# SCH1.net
KiCad netlist of a schematic drawn in EAGLE
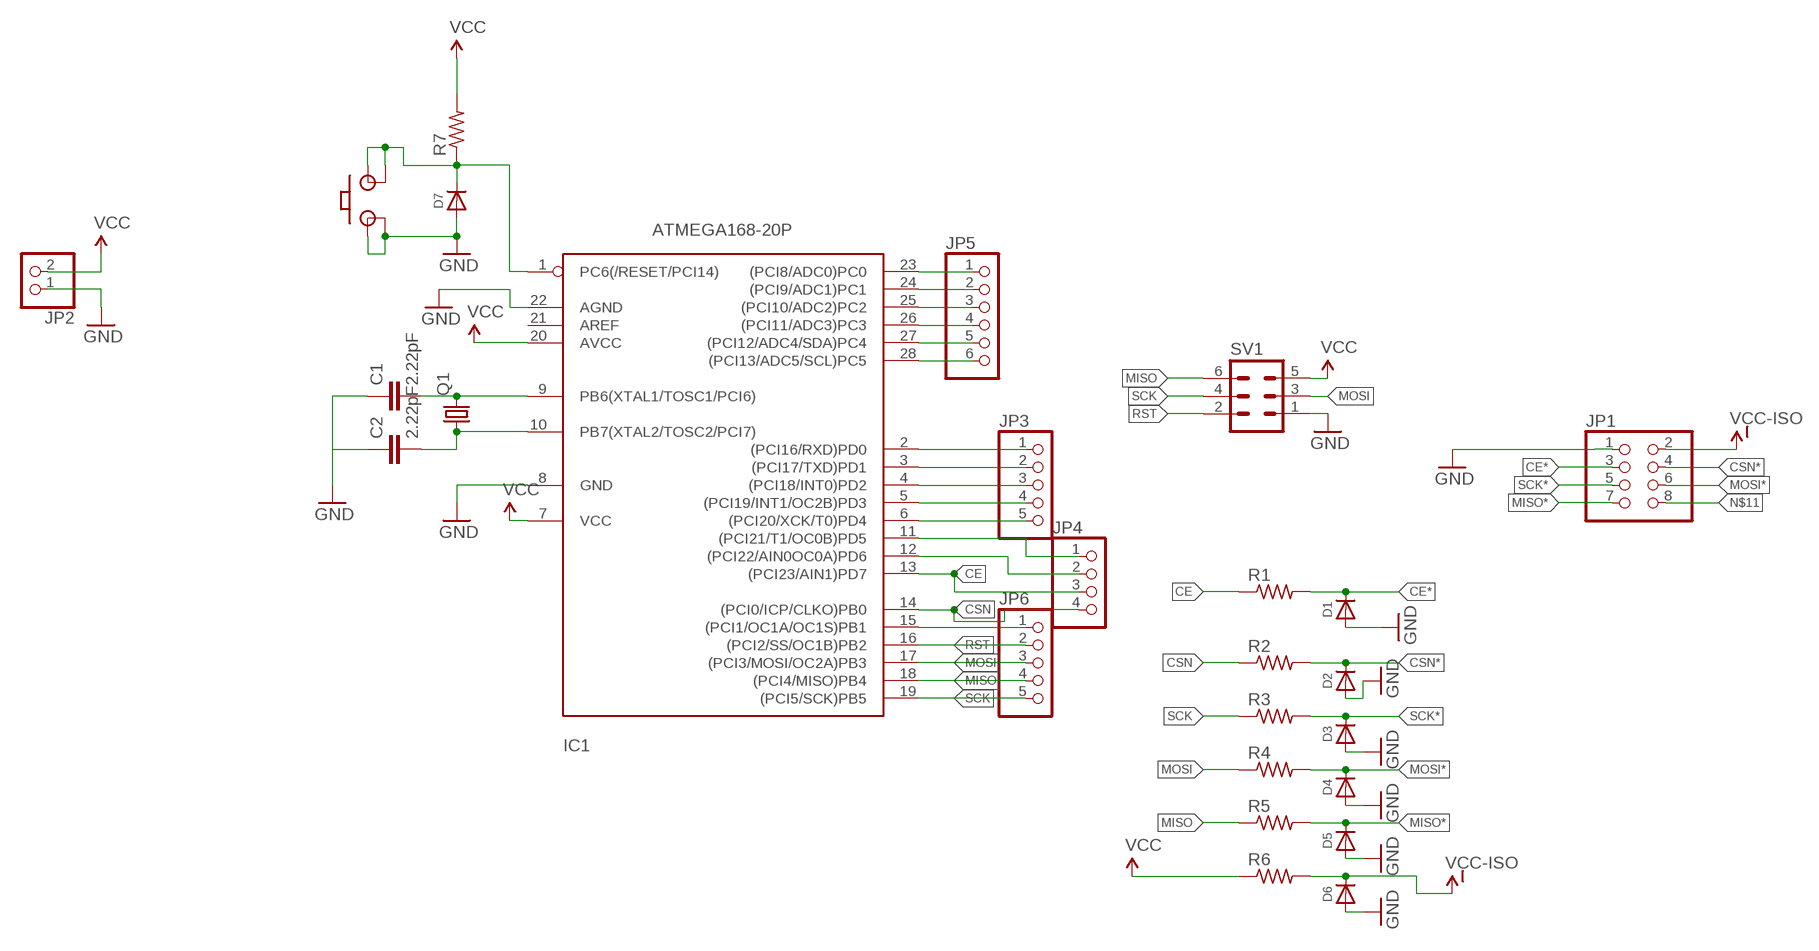
[diagram p0: schematic, sheet 1]

(export (version "E")
  (design (tool "Eeschema 10.0.6"))
  (components
    (comp (ref "C1")
      (value "2.22pF")
      (footprint "eagle-import:C025-024X044")
      (libsource (lib "eagle-import") (part "C-EU025-024X044"))
    )
    (comp (ref "C2")
      (value "2.22pF")
      (footprint "eagle-import:C025-024X044")
      (libsource (lib "eagle-import") (part "C-EU025-024X044"))
    )
    (comp (ref "D1")
      (value "DIODEDO-1N4148")
      (footprint "eagle-import:DO-1N4148")
      (libsource (lib "eagle-import") (part "DIODEDO-1N4148"))
    )
    (comp (ref "D2")
      (value "DIODEDO-1N4148")
      (footprint "eagle-import:DO-1N4148")
      (libsource (lib "eagle-import") (part "DIODEDO-1N4148"))
    )
    (comp (ref "D3")
      (value "DIODEDO-1N4148")
      (footprint "eagle-import:DO-1N4148")
      (libsource (lib "eagle-import") (part "DIODEDO-1N4148"))
    )
    (comp (ref "D4")
      (value "DIODEDO-1N4148")
      (footprint "eagle-import:DO-1N4148")
      (libsource (lib "eagle-import") (part "DIODEDO-1N4148"))
    )
    (comp (ref "D5")
      (value "DIODEDO-1N4148")
      (footprint "eagle-import:DO-1N4148")
      (libsource (lib "eagle-import") (part "DIODEDO-1N4148"))
    )
    (comp (ref "D6")
      (value "DIODEDO-1N4148")
      (footprint "eagle-import:DO-1N4148")
      (libsource (lib "eagle-import") (part "DIODEDO-1N4148"))
    )
    (comp (ref "D7")
      (value "DIODEDO-1N4148")
      (footprint "eagle-import:DO-1N4148")
      (libsource (lib "eagle-import") (part "DIODEDO-1N4148"))
    )
    (comp (ref "IC1")
      (value "ATMEGA168-20P")
      (footprint "eagle-import:DIL28-3")
      (libsource (lib "eagle-import") (part "ATMEGA168P-20"))
    )
    (comp (ref "JP1")
      (value "PINHD-2X4")
      (footprint "eagle-import:2X04")
      (libsource (lib "eagle-import") (part "PINHD-2X4"))
    )
    (comp (ref "JP2")
      (value "PINHD-1X2")
      (footprint "eagle-import:1X02")
      (libsource (lib "eagle-import") (part "PINHD-1X2"))
    )
    (comp (ref "JP3")
      (value "PINHD-1X5")
      (footprint "eagle-import:1X05")
      (libsource (lib "eagle-import") (part "PINHD-1X5"))
    )
    (comp (ref "JP4")
      (value "PINHD-1X4")
      (footprint "eagle-import:1X04")
      (libsource (lib "eagle-import") (part "PINHD-1X4"))
    )
    (comp (ref "JP5")
      (value "PINHD-1X6")
      (footprint "eagle-import:1X06")
      (libsource (lib "eagle-import") (part "PINHD-1X6"))
    )
    (comp (ref "JP6")
      (value "PINHD-1X5")
      (footprint "eagle-import:1X05")
      (libsource (lib "eagle-import") (part "PINHD-1X5"))
    )
    (comp (ref "PB1")
      (value "TACTSW")
      (footprint "eagle-import:TACTSW")
      (libsource (lib "eagle-import") (part "TACTSW"))
    )
    (comp (ref "Q1")
      (value "CRYSTALHC49U-V")
      (footprint "eagle-import:HC49U-V")
      (libsource (lib "eagle-import") (part "CRYSTALHC49U-V"))
    )
    (comp (ref "R1")
      (value "R-US_0207/7")
      (footprint "eagle-import:0207_7")
      (libsource (lib "eagle-import") (part "R-US_0207/7"))
    )
    (comp (ref "R2")
      (value "R-US_0207/7")
      (footprint "eagle-import:0207_7")
      (libsource (lib "eagle-import") (part "R-US_0207/7"))
    )
    (comp (ref "R3")
      (value "R-US_0207/7")
      (footprint "eagle-import:0207_7")
      (libsource (lib "eagle-import") (part "R-US_0207/7"))
    )
    (comp (ref "R4")
      (value "R-US_0207/7")
      (footprint "eagle-import:0207_7")
      (libsource (lib "eagle-import") (part "R-US_0207/7"))
    )
    (comp (ref "R5")
      (value "R-US_0207/7")
      (footprint "eagle-import:0207_7")
      (libsource (lib "eagle-import") (part "R-US_0207/7"))
    )
    (comp (ref "R6")
      (value "R-US_0207/7")
      (footprint "eagle-import:0207_7")
      (libsource (lib "eagle-import") (part "R-US_0207/7"))
    )
    (comp (ref "R7")
      (value "R-US_0207/7")
      (footprint "eagle-import:0207_7")
      (libsource (lib "eagle-import") (part "R-US_0207/7"))
    )
    (comp (ref "SV1")
      (value "MA03-2")
      (footprint "eagle-import:MA03-2")
      (libsource (lib "eagle-import") (part "MA03-2"))
    )
  )
  (nets
    (net (code "1") (name "CE") (class "Default")
      (node (ref "IC1") (pin "13") (pinfunction "(PCI23/AIN1)PD7_13") (pintype "bidirectional"))
      (node (ref "JP4") (pin "3") (pinfunction "3_3") (pintype "passive"))
      (node (ref "R1") (pin "1") (pinfunction "1_1") (pintype "passive"))
    )
    (net (code "2") (name "CE*") (class "Default")
      (node (ref "D1") (pin "C") (pinfunction "C_C") (pintype "passive"))
      (node (ref "JP1") (pin "3") (pinfunction "3_3") (pintype "passive"))
      (node (ref "R1") (pin "2") (pinfunction "2_2") (pintype "passive"))
    )
    (net (code "3") (name "CSN") (class "Default")
      (node (ref "IC1") (pin "14") (pinfunction "(PCI0/ICP/CLKO)PB0_14") (pintype "bidirectional"))
      (node (ref "JP4") (pin "4") (pinfunction "4_4") (pintype "passive"))
      (node (ref "R2") (pin "1") (pinfunction "1_1") (pintype "passive"))
    )
    (net (code "4") (name "CSN*") (class "Default")
      (node (ref "D2") (pin "C") (pinfunction "C_C") (pintype "passive"))
      (node (ref "JP1") (pin "4") (pinfunction "4_4") (pintype "passive"))
      (node (ref "R2") (pin "2") (pinfunction "2_2") (pintype "passive"))
    )
    (net (code "5") (name "GND") (class "Default")
      (node (ref "C1") (pin "1") (pinfunction "1_1") (pintype "passive"))
      (node (ref "C2") (pin "1") (pinfunction "1_1") (pintype "passive"))
      (node (ref "D1") (pin "A") (pinfunction "A_A") (pintype "passive"))
      (node (ref "D2") (pin "A") (pinfunction "A_A") (pintype "passive"))
      (node (ref "D3") (pin "A") (pinfunction "A_A") (pintype "passive"))
      (node (ref "D4") (pin "A") (pinfunction "A_A") (pintype "passive"))
      (node (ref "D5") (pin "A") (pinfunction "A_A") (pintype "passive"))
      (node (ref "D6") (pin "A") (pinfunction "A_A") (pintype "passive"))
      (node (ref "D7") (pin "A") (pinfunction "A_A") (pintype "passive"))
      (node (ref "IC1") (pin "22") (pinfunction "AGND_22") (pintype "bidirectional"))
      (node (ref "IC1") (pin "8") (pinfunction "GND_8") (pintype "bidirectional"))
      (node (ref "JP1") (pin "1") (pinfunction "1_1") (pintype "passive"))
      (node (ref "JP2") (pin "1") (pinfunction "1_1") (pintype "passive"))
      (node (ref "PB1") (pin "P$1") (pinfunction "P$1_P$1") (pintype "passive"))
      (node (ref "PB1") (pin "P$2") (pinfunction "P$3_P$2") (pintype "passive"))
      (node (ref "SV1") (pin "1") (pinfunction "1_1") (pintype "passive"))
    )
    (net (code "6") (name "MISO") (class "Default")
      (node (ref "IC1") (pin "18") (pinfunction "(PCI4/MISO)PB4_18") (pintype "bidirectional"))
      (node (ref "JP6") (pin "4") (pinfunction "4_4") (pintype "passive"))
      (node (ref "R5") (pin "1") (pinfunction "1_1") (pintype "passive"))
      (node (ref "SV1") (pin "6") (pinfunction "6_6") (pintype "passive"))
    )
    (net (code "7") (name "MISO*") (class "Default")
      (node (ref "D5") (pin "C") (pinfunction "C_C") (pintype "passive"))
      (node (ref "JP1") (pin "7") (pinfunction "7_7") (pintype "passive"))
      (node (ref "R5") (pin "2") (pinfunction "2_2") (pintype "passive"))
    )
    (net (code "8") (name "MOSI") (class "Default")
      (node (ref "IC1") (pin "17") (pinfunction "(PCI3/MOSI/OC2A)PB3_17") (pintype "bidirectional"))
      (node (ref "JP6") (pin "3") (pinfunction "3_3") (pintype "passive"))
      (node (ref "R4") (pin "1") (pinfunction "1_1") (pintype "passive"))
      (node (ref "SV1") (pin "3") (pinfunction "3_3") (pintype "passive"))
    )
    (net (code "9") (name "MOSI*") (class "Default")
      (node (ref "D4") (pin "C") (pinfunction "C_C") (pintype "passive"))
      (node (ref "JP1") (pin "6") (pinfunction "6_6") (pintype "passive"))
      (node (ref "R4") (pin "2") (pinfunction "2_2") (pintype "passive"))
    )
    (net (code "10") (name "N$11") (class "Default")
      (node (ref "JP1") (pin "8") (pinfunction "8_8") (pintype "passive"))
    )
    (net (code "11") (name "Net-(IC1-(PCI1{slash}OC1A{slash}OC1S)PB1)") (class "Default")
      (node (ref "IC1") (pin "15") (pinfunction "(PCI1/OC1A/OC1S)PB1_15") (pintype "bidirectional"))
      (node (ref "JP6") (pin "1") (pinfunction "1_1") (pintype "passive"))
    )
    (net (code "12") (name "Net-(IC1-(PCI8{slash}ADC0)PC0)") (class "Default")
      (node (ref "IC1") (pin "23") (pinfunction "(PCI8/ADC0)PC0_23") (pintype "bidirectional"))
      (node (ref "JP5") (pin "1") (pinfunction "1_1") (pintype "passive"))
    )
    (net (code "13") (name "Net-(IC1-(PCI9{slash}ADC1)PC1)") (class "Default")
      (node (ref "IC1") (pin "24") (pinfunction "(PCI9/ADC1)PC1_24") (pintype "bidirectional"))
      (node (ref "JP5") (pin "2") (pinfunction "2_2") (pintype "passive"))
    )
    (net (code "14") (name "Net-(IC1-(PCI10{slash}ADC2)PC2)") (class "Default")
      (node (ref "IC1") (pin "25") (pinfunction "(PCI10/ADC2)PC2_25") (pintype "bidirectional"))
      (node (ref "JP5") (pin "3") (pinfunction "3_3") (pintype "passive"))
    )
    (net (code "15") (name "Net-(IC1-(PCI11{slash}ADC3)PC3)") (class "Default")
      (node (ref "IC1") (pin "26") (pinfunction "(PCI11/ADC3)PC3_26") (pintype "bidirectional"))
      (node (ref "JP5") (pin "4") (pinfunction "4_4") (pintype "passive"))
    )
    (net (code "16") (name "Net-(IC1-(PCI12{slash}ADC4{slash}SDA)PC4)") (class "Default")
      (node (ref "IC1") (pin "27") (pinfunction "(PCI12/ADC4/SDA)PC4_27") (pintype "bidirectional"))
      (node (ref "JP5") (pin "5") (pinfunction "5_5") (pintype "passive"))
    )
    (net (code "17") (name "Net-(IC1-(PCI13{slash}ADC5{slash}SCL)PC5)") (class "Default")
      (node (ref "IC1") (pin "28") (pinfunction "(PCI13/ADC5/SCL)PC5_28") (pintype "bidirectional"))
      (node (ref "JP5") (pin "6") (pinfunction "6_6") (pintype "passive"))
    )
    (net (code "18") (name "Net-(IC1-(PCI16{slash}RXD)PD0)") (class "Default")
      (node (ref "IC1") (pin "2") (pinfunction "(PCI16/RXD)PD0_2") (pintype "bidirectional"))
      (node (ref "JP3") (pin "1") (pinfunction "1_1") (pintype "passive"))
    )
    (net (code "19") (name "Net-(IC1-(PCI17{slash}TXD)PD1)") (class "Default")
      (node (ref "IC1") (pin "3") (pinfunction "(PCI17/TXD)PD1_3") (pintype "bidirectional"))
      (node (ref "JP3") (pin "2") (pinfunction "2_2") (pintype "passive"))
    )
    (net (code "20") (name "Net-(IC1-(PCI18{slash}INT0)PD2)") (class "Default")
      (node (ref "IC1") (pin "4") (pinfunction "(PCI18/INT0)PD2_4") (pintype "bidirectional"))
      (node (ref "JP3") (pin "3") (pinfunction "3_3") (pintype "passive"))
    )
    (net (code "21") (name "Net-(IC1-(PCI19{slash}INT1{slash}OC2B)PD3)") (class "Default")
      (node (ref "IC1") (pin "5") (pinfunction "(PCI19/INT1/OC2B)PD3_5") (pintype "bidirectional"))
      (node (ref "JP3") (pin "4") (pinfunction "4_4") (pintype "passive"))
    )
    (net (code "22") (name "Net-(IC1-(PCI20{slash}XCK{slash}T0)PD4)") (class "Default")
      (node (ref "IC1") (pin "6") (pinfunction "(PCI20/XCK/T0)PD4_6") (pintype "bidirectional"))
      (node (ref "JP3") (pin "5") (pinfunction "5_5") (pintype "passive"))
    )
    (net (code "23") (name "Net-(IC1-(PCI21{slash}T1{slash}OC0B)PD5)") (class "Default")
      (node (ref "IC1") (pin "11") (pinfunction "(PCI21/T1/OC0B)PD5_11") (pintype "bidirectional"))
      (node (ref "JP4") (pin "1") (pinfunction "1_1") (pintype "passive"))
    )
    (net (code "24") (name "Net-(IC1-(PCI22{slash}AIN0OC0A)PD6)") (class "Default")
      (node (ref "IC1") (pin "12") (pinfunction "(PCI22/AIN0OC0A)PD6_12") (pintype "bidirectional"))
      (node (ref "JP4") (pin "2") (pinfunction "2_2") (pintype "passive"))
    )
    (net (code "25") (name "Net-(IC1-PB6(XTAL1{slash}TOSC1{slash}PCI6))") (class "Default")
      (node (ref "C1") (pin "2") (pinfunction "2_2") (pintype "passive"))
      (node (ref "IC1") (pin "9") (pinfunction "PB6(XTAL1/TOSC1/PCI6)_9") (pintype "bidirectional"))
      (node (ref "Q1") (pin "2") (pinfunction "2_2") (pintype "passive"))
    )
    (net (code "26") (name "Net-(IC1-PB7(XTAL2{slash}TOSC2{slash}PCI7))") (class "Default")
      (node (ref "C2") (pin "2") (pinfunction "2_2") (pintype "passive"))
      (node (ref "IC1") (pin "10") (pinfunction "PB7(XTAL2/TOSC2/PCI7)_10") (pintype "bidirectional"))
      (node (ref "Q1") (pin "1") (pinfunction "1_1") (pintype "passive"))
    )
    (net (code "27") (name "Net-(IC1-PC6({slash}RESET{slash}PCI14))") (class "Default")
      (node (ref "D7") (pin "C") (pinfunction "C_C") (pintype "passive"))
      (node (ref "IC1") (pin "1") (pinfunction "PC6(/RESET/PCI14)_1") (pintype "bidirectional"))
      (node (ref "PB1") (pin "P$3") (pinfunction "P$2_P$3") (pintype "passive"))
      (node (ref "PB1") (pin "P$4") (pinfunction "P$4_P$4") (pintype "passive"))
      (node (ref "R7") (pin "1") (pinfunction "1_1") (pintype "passive"))
    )
    (net (code "28") (name "RST") (class "Default")
      (node (ref "IC1") (pin "16") (pinfunction "(PCI2/SS/OC1B)PB2_16") (pintype "bidirectional"))
      (node (ref "JP6") (pin "2") (pinfunction "2_2") (pintype "passive"))
      (node (ref "SV1") (pin "2") (pinfunction "2_2") (pintype "passive"))
    )
    (net (code "29") (name "SCK") (class "Default")
      (node (ref "IC1") (pin "19") (pinfunction "(PCI5/SCK)PB5_19") (pintype "bidirectional"))
      (node (ref "JP6") (pin "5") (pinfunction "5_5") (pintype "passive"))
      (node (ref "R3") (pin "1") (pinfunction "1_1") (pintype "passive"))
      (node (ref "SV1") (pin "4") (pinfunction "4_4") (pintype "passive"))
    )
    (net (code "30") (name "SCK*") (class "Default")
      (node (ref "D3") (pin "C") (pinfunction "C_C") (pintype "passive"))
      (node (ref "JP1") (pin "5") (pinfunction "5_5") (pintype "passive"))
      (node (ref "R3") (pin "2") (pinfunction "2_2") (pintype "passive"))
    )
    (net (code "31") (name "VCC") (class "Default")
      (node (ref "IC1") (pin "20") (pinfunction "AVCC_20") (pintype "bidirectional"))
      (node (ref "IC1") (pin "7") (pinfunction "VCC_7") (pintype "bidirectional"))
      (node (ref "JP2") (pin "2") (pinfunction "2_2") (pintype "passive"))
      (node (ref "R6") (pin "1") (pinfunction "1_1") (pintype "passive"))
      (node (ref "R7") (pin "2") (pinfunction "2_2") (pintype "passive"))
      (node (ref "SV1") (pin "5") (pinfunction "5_5") (pintype "passive"))
    )
    (net (code "32") (name "VCC-ISO") (class "Default")
      (node (ref "D6") (pin "C") (pinfunction "C_C") (pintype "passive"))
      (node (ref "JP1") (pin "2") (pinfunction "2_2") (pintype "passive"))
      (node (ref "R6") (pin "2") (pinfunction "2_2") (pintype "passive"))
    )
    (net (code "33") (name "unconnected-(IC1-AREF-Pad21)") (class "Default")
      (node (ref "IC1") (pin "21") (pinfunction "AREF_21") (pintype "bidirectional"))
    )
  )
)
